# 13_-BACKUP_POWER.net
KiCad netlist of a schematic drawn in Altium Designer
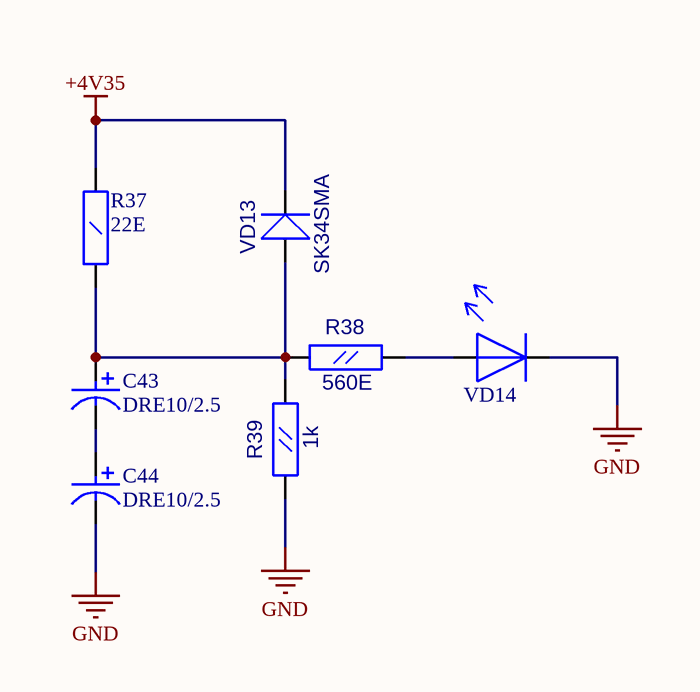
[diagram p0: [13]-BACKUP_POWER.SchDoc]

(export (version "E")
  (design (tool "Eeschema 10.0.6"))
  (components
    (comp (ref "C43")
      (value "DRE10/2.5")
      (footprint "CAP_13x26")
      (libsource (lib "fizik_lib") (part "SUPERCAP_10F"))
    )
    (comp (ref "C44")
      (value "DRE10/2.5")
      (footprint "CAP_13x26")
      (libsource (lib "fizik_lib") (part "SUPERCAP_10F"))
    )
    (comp (ref "R37")
      (value "22E")
      (footprint "R2512")
      (description "Resistor 2512 1W")
      (libsource (lib "fizik_lib") (part "RC2512"))
    )
    (comp (ref "R38")
      (value "560E")
      (footprint "RC0603")
      (description "RC0603")
      (libsource (lib "fizik_lib") (part "RC0603"))
    )
    (comp (ref "R39")
      (value "1k")
      (footprint "RC0603")
      (description "RC0603")
      (libsource (lib "fizik_lib") (part "RC0603"))
    )
    (comp (ref "VD13")
      (value "SK34SMA")
      (footprint "SMA")
      (description "Schottky Rectifier")
      (libsource (lib "gprs_modem") (part "SK34SMA"))
    )
    (comp (ref "VD14")
      (value "LED_0805")
      (footprint "LED0805")
      (libsource (lib "fizik_lib") (part "LED_0805"))
    )
  )
  (nets
    (net (code "1") (name "+4V35") (class "Default")
      (node (ref "R37") (pin "2") (pinfunction "B_2") (pintype "passive"))
      (node (ref "VD13") (pin "2") (pinfunction "K_2") (pintype "passive"))
    )
    (net (code "2") (name "GND") (class "Default")
      (node (ref "C44") (pin "1") (pintype "passive"))
      (node (ref "R39") (pin "1") (pinfunction "A_1") (pintype "passive"))
      (node (ref "VD14") (pin "2") (pintype "passive"))
    )
    (net (code "3") (name "Net-(C43-Pad1)") (class "Default")
      (node (ref "C43") (pin "1") (pintype "passive"))
      (node (ref "C44") (pin "2") (pintype "passive"))
    )
    (net (code "4") (name "Net-(R37-A)") (class "Default")
      (node (ref "C43") (pin "2") (pintype "passive"))
      (node (ref "R37") (pin "1") (pinfunction "A_1") (pintype "passive"))
      (node (ref "R38") (pin "1") (pinfunction "A_1") (pintype "passive"))
      (node (ref "R39") (pin "2") (pinfunction "B_2") (pintype "passive"))
      (node (ref "VD13") (pin "1") (pinfunction "A_1") (pintype "passive"))
    )
    (net (code "5") (name "Net-(R38-B)") (class "Default")
      (node (ref "R38") (pin "2") (pinfunction "B_2") (pintype "passive"))
      (node (ref "VD14") (pin "1") (pintype "passive"))
    )
  )
)
